# UNOCompatibleBoard.net
KiCad netlist of a schematic drawn in Altium Designer
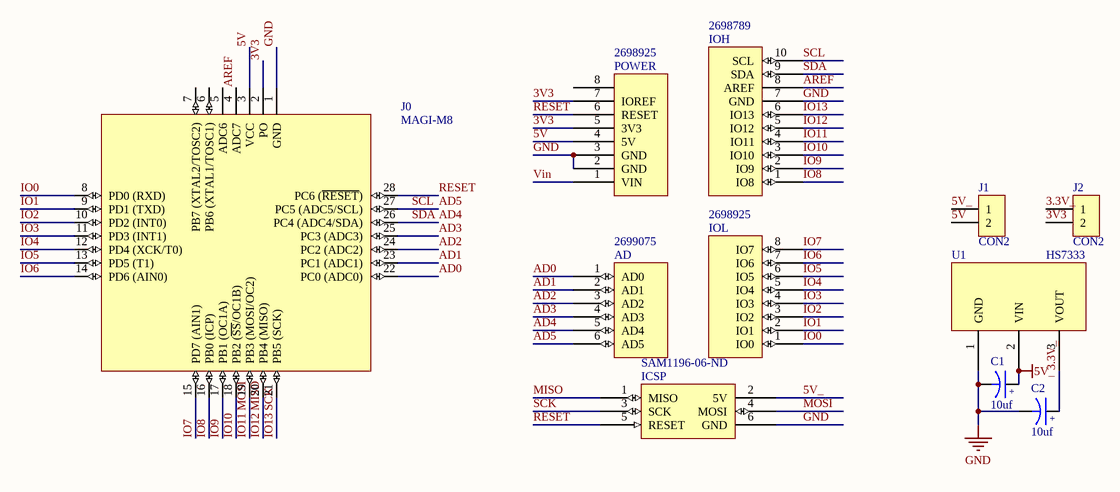
[diagram p0: UNOCompatibleBoard.SchDoc]

(export (version "E")
  (design (tool "Eeschema 10.0.6"))
  (components
    (comp (ref "AD")
      (value "AD")
      (footprint "Header:Header 6x1 8.5mm")
      (fields (field (name "SUPPLIER PART NUMBER 4") "2699075"))
      (libsource (lib "Header") (part "AD"))
    )
    (comp (ref "C1")
      (value "10uf")
      (footprint "6-0805_N")
      (description "Capacitor")
      (libsource (lib "电容器") (part "CAPACITOR POL"))
    )
    (comp (ref "C2")
      (value "10uf")
      (footprint "6-0805_N")
      (description "Capacitor")
      (libsource (lib "电容器") (part "CAPACITOR POL"))
    )
    (comp (ref "ICSP")
      (value "ICSP")
      (footprint "ICSP")
      (fields (field (name "SUPPLIER PART NUMBER 5") "SAM1196-06-ND"))
      (libsource (lib "Header") (part "ICSP"))
    )
    (comp (ref "IOH")
      (value "IOH")
      (footprint "Header:Header 10x1 8.5mm")
      (fields (field (name "SUPPLIER PART NUMBER 3") "2698789"))
      (libsource (lib "Header") (part "IOH"))
    )
    (comp (ref "IOL")
      (value "IOL")
      (footprint "Header 8x1 8.5mm")
      (fields (field (name "SUPPLIER PART NUMBER 4") "2698925"))
      (libsource (lib "Header") (part "IOL"))
    )
    (comp (ref "J0") (value "MAGI-M8") (footprint "MAGI-M8") (libsource (lib "MAGI-M8") (part "MAGI-M8")))
    (comp (ref "J1")
      (value "CON2")
      (footprint "SIP2")
      (description "Connector")
      (libsource (lib "CON系列") (part "CON2"))
    )
    (comp (ref "J2")
      (value "CON2")
      (footprint "sip2")
      (description "Connector")
      (libsource (lib "CON系列") (part "CON2"))
    )
    (comp (ref "POWER")
      (value "POWER_UNO")
      (footprint "Header 8x1 8.5mm")
      (fields (field (name "SUPPLIER PART NUMBER 4") "2698925"))
      (libsource (lib "Header") (part "POWER_UNO"))
    )
    (comp (ref "U1") (value "HS7333") (footprint "HS7333") (libsource (lib "PMIC") (part "HS7333")))
  )
  (nets
    (net (code "1") (name "/3.3V_") (class "Default")
      (node (ref "C2") (pin "1") (pinfunction "1_1") (pintype "passive"))
      (node (ref "J2") (pin "1") (pinfunction "1_1") (pintype "passive"))
      (node (ref "U1") (pin "3") (pinfunction "VOUT_3") (pintype "passive"))
    )
    (net (code "2") (name "/3V3") (class "Default")
      (node (ref "J0") (pin "2") (pinfunction "PO_2") (pintype "power_in"))
      (node (ref "J2") (pin "2") (pinfunction "2_2") (pintype "passive"))
      (node (ref "POWER") (pin "5") (pinfunction "3V3_5") (pintype "power_in"))
      (node (ref "POWER") (pin "7") (pinfunction "IOREF_7") (pintype "power_in"))
    )
    (net (code "3") (name "/5V") (class "Default")
      (node (ref "J0") (pin "3") (pinfunction "VCC_3") (pintype "power_in"))
      (node (ref "J1") (pin "2") (pinfunction "2_2") (pintype "passive"))
      (node (ref "POWER") (pin "4") (pinfunction "5V_4") (pintype "power_in"))
    )
    (net (code "5") (name "/AD0") (class "Default")
      (node (ref "AD") (pin "1") (pinfunction "AD0_1") (pintype "bidirectional"))
      (node (ref "J0") (pin "22") (pinfunction "PC0_(ADC0)_22") (pintype "bidirectional"))
    )
    (net (code "6") (name "/AD1") (class "Default")
      (node (ref "AD") (pin "2") (pinfunction "AD1_2") (pintype "bidirectional"))
      (node (ref "J0") (pin "23") (pinfunction "PC1_(ADC1)_23") (pintype "bidirectional"))
    )
    (net (code "7") (name "/AD2") (class "Default")
      (node (ref "AD") (pin "3") (pinfunction "AD2_3") (pintype "bidirectional"))
      (node (ref "J0") (pin "24") (pinfunction "PC2_(ADC2)_24") (pintype "bidirectional"))
    )
    (net (code "8") (name "/AD3") (class "Default")
      (node (ref "AD") (pin "4") (pinfunction "AD3_4") (pintype "bidirectional"))
      (node (ref "J0") (pin "25") (pinfunction "PC3_(ADC3)_25") (pintype "bidirectional"))
    )
    (net (code "9") (name "/AD4") (class "Default")
      (node (ref "AD") (pin "5") (pinfunction "AD4_5") (pintype "bidirectional"))
      (node (ref "IOH") (pin "9") (pinfunction "SDA_9") (pintype "bidirectional"))
      (node (ref "J0") (pin "26") (pinfunction "PC4_(ADC4/SDA)_26") (pintype "bidirectional"))
    )
    (net (code "10") (name "/AD5") (class "Default")
      (node (ref "AD") (pin "6") (pinfunction "AD5_6") (pintype "bidirectional"))
      (node (ref "IOH") (pin "10") (pinfunction "SCL_10") (pintype "bidirectional"))
      (node (ref "J0") (pin "27") (pinfunction "PC5_(ADC5/SCL)_27") (pintype "bidirectional"))
    )
    (net (code "11") (name "/AREF") (class "Default")
      (node (ref "IOH") (pin "8") (pinfunction "AREF_8") (pintype "passive"))
      (node (ref "J0") (pin "4") (pinfunction "ADC7_4") (pintype "passive"))
    )
    (net (code "12") (name "/IO0") (class "Default")
      (node (ref "IOL") (pin "1") (pinfunction "IO0_1") (pintype "bidirectional"))
      (node (ref "J0") (pin "8") (pinfunction "PD0_(RXD)_8") (pintype "bidirectional"))
    )
    (net (code "13") (name "/IO1") (class "Default")
      (node (ref "IOL") (pin "2") (pinfunction "IO1_2") (pintype "bidirectional"))
      (node (ref "J0") (pin "9") (pinfunction "PD1_(TXD)_9") (pintype "bidirectional"))
    )
    (net (code "14") (name "/IO2") (class "Default")
      (node (ref "IOL") (pin "3") (pinfunction "IO2_3") (pintype "bidirectional"))
      (node (ref "J0") (pin "10") (pinfunction "PD2_(INT0)_10") (pintype "bidirectional"))
    )
    (net (code "15") (name "/IO3") (class "Default")
      (node (ref "IOL") (pin "4") (pinfunction "IO3_4") (pintype "bidirectional"))
      (node (ref "J0") (pin "11") (pinfunction "PD3_(INT1)_11") (pintype "bidirectional"))
    )
    (net (code "16") (name "/IO4") (class "Default")
      (node (ref "IOL") (pin "5") (pinfunction "IO4_5") (pintype "bidirectional"))
      (node (ref "J0") (pin "12") (pinfunction "PD4_(XCK/T0)_12") (pintype "bidirectional"))
    )
    (net (code "17") (name "/IO5") (class "Default")
      (node (ref "IOL") (pin "6") (pinfunction "IO5_6") (pintype "bidirectional"))
      (node (ref "J0") (pin "13") (pinfunction "PD5_(T1)_13") (pintype "bidirectional"))
    )
    (net (code "18") (name "/IO6") (class "Default")
      (node (ref "IOL") (pin "7") (pinfunction "IO6_7") (pintype "bidirectional"))
      (node (ref "J0") (pin "14") (pinfunction "PD6_(AIN0)_14") (pintype "bidirectional"))
    )
    (net (code "19") (name "/IO7") (class "Default")
      (node (ref "IOL") (pin "8") (pinfunction "IO7_8") (pintype "bidirectional"))
      (node (ref "J0") (pin "15") (pinfunction "PD7_(AIN1)_15") (pintype "bidirectional"))
    )
    (net (code "20") (name "/IO8") (class "Default")
      (node (ref "IOH") (pin "1") (pinfunction "IO8_1") (pintype "bidirectional"))
      (node (ref "J0") (pin "16") (pinfunction "PB0_(ICP)_16") (pintype "bidirectional"))
    )
    (net (code "21") (name "/IO9") (class "Default")
      (node (ref "IOH") (pin "2") (pinfunction "IO9_2") (pintype "bidirectional"))
      (node (ref "J0") (pin "17") (pinfunction "PB1_(OC1A)_17") (pintype "bidirectional"))
    )
    (net (code "22") (name "/IO10") (class "Default")
      (node (ref "IOH") (pin "3") (pinfunction "IO10_3") (pintype "bidirectional"))
      (node (ref "J0") (pin "18") (pinfunction "PB2_(~{SS}/OC1B)_18") (pintype "bidirectional"))
    )
    (net (code "23") (name "/IO11") (class "Default")
      (node (ref "ICSP") (pin "4") (pinfunction "MOSI_4") (pintype "bidirectional"))
      (node (ref "IOH") (pin "4") (pinfunction "IO11_4") (pintype "bidirectional"))
      (node (ref "J0") (pin "19") (pinfunction "PB3_(MOSI/OC2)_19") (pintype "bidirectional"))
    )
    (net (code "24") (name "/IO12") (class "Default")
      (node (ref "ICSP") (pin "1") (pinfunction "MISO_1") (pintype "bidirectional"))
      (node (ref "IOH") (pin "5") (pinfunction "IO12_5") (pintype "bidirectional"))
      (node (ref "J0") (pin "20") (pinfunction "PB4_(MISO)_20") (pintype "bidirectional"))
    )
    (net (code "25") (name "/IO13") (class "Default")
      (node (ref "ICSP") (pin "3") (pinfunction "SCK_3") (pintype "bidirectional"))
      (node (ref "IOH") (pin "6") (pinfunction "IO13_6") (pintype "bidirectional"))
      (node (ref "J0") (pin "21") (pinfunction "PB5_(SCK)_21") (pintype "bidirectional"))
    )
    (net (code "26") (name "/RESET") (class "Default")
      (node (ref "ICSP") (pin "5") (pinfunction "RESET_5") (pintype "input"))
      (node (ref "J0") (pin "28") (pinfunction "PC6_(~{RESET})_28") (pintype "bidirectional"))
      (node (ref "POWER") (pin "6") (pinfunction "RESET_6") (pintype "passive"))
    )
    (net (code "27") (name "/Vin") (class "Default")
      (node (ref "POWER") (pin "1") (pinfunction "VIN_1") (pintype "power_in"))
    )
    (net (code "28") (name "5V_") (class "Default")
      (node (ref "C1") (pin "1") (pinfunction "1_1") (pintype "passive"))
      (node (ref "ICSP") (pin "2") (pinfunction "5V_2") (pintype "power_in"))
      (node (ref "J1") (pin "1") (pinfunction "1_1") (pintype "passive"))
      (node (ref "U1") (pin "2") (pinfunction "VIN_2") (pintype "passive"))
    )
    (net (code "29") (name "GND") (class "Default")
      (node (ref "C1") (pin "2") (pinfunction "2_2") (pintype "passive"))
      (node (ref "C2") (pin "2") (pinfunction "2_2") (pintype "passive"))
      (node (ref "ICSP") (pin "6") (pinfunction "GND_6") (pintype "power_in"))
      (node (ref "IOH") (pin "7") (pinfunction "GND_7") (pintype "power_in"))
      (node (ref "J0") (pin "1") (pinfunction "GND_1") (pintype "power_in"))
      (node (ref "POWER") (pin "2") (pinfunction "GND_2") (pintype "power_in"))
      (node (ref "POWER") (pin "3") (pinfunction "GND_3") (pintype "power_in"))
      (node (ref "U1") (pin "1") (pinfunction "GND_1") (pintype "passive"))
    )
    (net (code "30") (name "unconnected-(J0-ADC6-Pad5)") (class "Default")
      (node (ref "J0") (pin "5") (pinfunction "ADC6_5") (pintype "passive"))
    )
    (net (code "31") (name "unconnected-(J0-PB6_(XTAL1{slash}TOSC1)-Pad6)") (class "Default")
      (node (ref "J0") (pin "6") (pinfunction "PB6_(XTAL1/TOSC1)_6") (pintype "bidirectional"))
    )
    (net (code "32") (name "unconnected-(J0-PB7_(XTAL2{slash}TOSC2)-Pad7)") (class "Default")
      (node (ref "J0") (pin "7") (pinfunction "PB7_(XTAL2/TOSC2)_7") (pintype "bidirectional"))
    )
    (net (code "33") (name "unconnected-(POWER-Pad8)") (class "Default")
      (node (ref "POWER") (pin "8") (pintype "passive"))
    )
  )
)
